# prefab.net
KiCad netlist of a schematic drawn in EAGLE
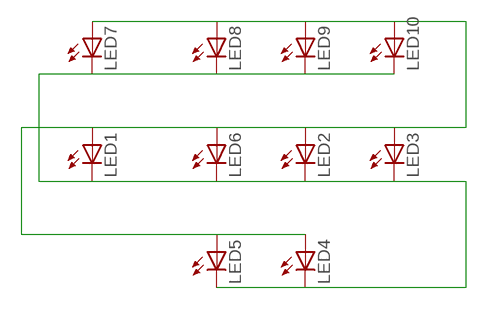
[diagram p0: schematic, sheet 1]

(export (version "E")
  (design (tool "Eeschema 10.0.6"))
  (components
    (comp (ref "LED1")
      (value "LED1206")
      (footprint "eagle-import:LED-1206")
      (libsource (lib "eagle-import") (part "LED1206"))
    )
    (comp (ref "LED2")
      (value "LED1206")
      (footprint "eagle-import:LED-1206")
      (libsource (lib "eagle-import") (part "LED1206"))
    )
    (comp (ref "LED3")
      (value "LED1206")
      (footprint "eagle-import:LED-1206")
      (libsource (lib "eagle-import") (part "LED1206"))
    )
    (comp (ref "LED4")
      (value "LED1206")
      (footprint "eagle-import:LED-1206")
      (libsource (lib "eagle-import") (part "LED1206"))
    )
    (comp (ref "LED5")
      (value "LED1206")
      (footprint "eagle-import:LED-1206")
      (libsource (lib "eagle-import") (part "LED1206"))
    )
    (comp (ref "LED6")
      (value "LED1206")
      (footprint "eagle-import:LED-1206")
      (libsource (lib "eagle-import") (part "LED1206"))
    )
    (comp (ref "LED7")
      (value "LED1206")
      (footprint "eagle-import:LED-1206")
      (libsource (lib "eagle-import") (part "LED1206"))
    )
    (comp (ref "LED8")
      (value "LED1206")
      (footprint "eagle-import:LED-1206")
      (libsource (lib "eagle-import") (part "LED1206"))
    )
    (comp (ref "LED9")
      (value "LED1206")
      (footprint "eagle-import:LED-1206")
      (libsource (lib "eagle-import") (part "LED1206"))
    )
    (comp (ref "LED10")
      (value "LED1206")
      (footprint "eagle-import:LED-1206")
      (libsource (lib "eagle-import") (part "LED1206"))
    )
  )
  (nets
    (net (code "1") (name "Net-(LED1-PadA)") (class "Default")
      (node (ref "LED1") (pin "A") (pinfunction "A_A") (pintype "passive"))
      (node (ref "LED10") (pin "A") (pinfunction "A_A") (pintype "passive"))
      (node (ref "LED2") (pin "A") (pinfunction "A_A") (pintype "passive"))
      (node (ref "LED3") (pin "A") (pinfunction "A_A") (pintype "passive"))
      (node (ref "LED4") (pin "A") (pinfunction "A_A") (pintype "passive"))
      (node (ref "LED5") (pin "A") (pinfunction "A_A") (pintype "passive"))
      (node (ref "LED6") (pin "A") (pinfunction "A_A") (pintype "passive"))
      (node (ref "LED7") (pin "A") (pinfunction "A_A") (pintype "passive"))
      (node (ref "LED8") (pin "A") (pinfunction "A_A") (pintype "passive"))
      (node (ref "LED9") (pin "A") (pinfunction "A_A") (pintype "passive"))
    )
    (net (code "2") (name "Net-(LED1-PadC)") (class "Default")
      (node (ref "LED1") (pin "C") (pinfunction "C_C") (pintype "passive"))
      (node (ref "LED10") (pin "C") (pinfunction "C_C") (pintype "passive"))
      (node (ref "LED2") (pin "C") (pinfunction "C_C") (pintype "passive"))
      (node (ref "LED3") (pin "C") (pinfunction "C_C") (pintype "passive"))
      (node (ref "LED4") (pin "C") (pinfunction "C_C") (pintype "passive"))
      (node (ref "LED5") (pin "C") (pinfunction "C_C") (pintype "passive"))
      (node (ref "LED6") (pin "C") (pinfunction "C_C") (pintype "passive"))
      (node (ref "LED7") (pin "C") (pinfunction "C_C") (pintype "passive"))
      (node (ref "LED8") (pin "C") (pinfunction "C_C") (pintype "passive"))
      (node (ref "LED9") (pin "C") (pinfunction "C_C") (pintype "passive"))
    )
  )
)
